# board.net
KiCad netlist of a schematic drawn in EAGLE
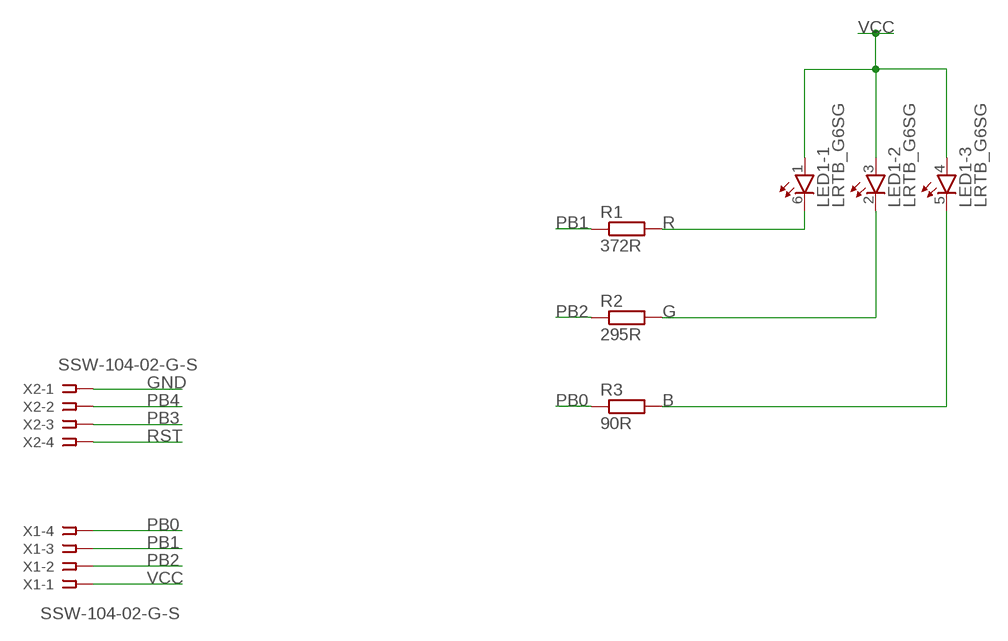
[diagram p0: schematic, sheet 1]

(export (version "E")
  (design (tool "Eeschema 10.0.6"))
  (components
    (comp (ref "LED1")
      (value "LRTB_G6SG")
      (footprint "eagle-import:LRTB_G6SG")
      (libsource (lib "eagle-import") (part "LRTB_G6SG"))
    )
    (comp (ref "R1")
      (value "372R")
      (footprint "eagle-import:R1206")
      (libsource (lib "eagle-import") (part "R-EU_R1206"))
    )
    (comp (ref "R2")
      (value "295R")
      (footprint "eagle-import:R1206")
      (libsource (lib "eagle-import") (part "R-EU_R1206"))
    )
    (comp (ref "R3")
      (value "90R")
      (footprint "eagle-import:R1206")
      (libsource (lib "eagle-import") (part "R-EU_R1206"))
    )
    (comp (ref "X1")
      (value "SSW-104-02-G-S")
      (footprint "eagle-import:SSW-104-02-G-S")
      (fields (field (name "MF") "Samtec Inc."))
      (libsource (lib "eagle-import") (part "SSW-104-02-G-S"))
    )
    (comp (ref "X2")
      (value "SSW-104-02-G-S")
      (footprint "eagle-import:SSW-104-02-G-S")
      (fields (field (name "MF") "Samtec Inc."))
      (libsource (lib "eagle-import") (part "SSW-104-02-G-S"))
    )
  )
  (nets
    (net (code "1") (name "/B") (class "Default")
      (node (ref "LED1") (pin "5") (pinfunction "C_5") (pintype "passive"))
      (node (ref "R3") (pin "2") (pinfunction "2_2") (pintype "passive"))
    )
    (net (code "2") (name "/G") (class "Default")
      (node (ref "LED1") (pin "2") (pinfunction "C_2") (pintype "passive"))
      (node (ref "R2") (pin "2") (pinfunction "2_2") (pintype "passive"))
    )
    (net (code "3") (name "/GND") (class "Default")
      (node (ref "X2") (pin "1") (pinfunction "1_1") (pintype "passive"))
    )
    (net (code "4") (name "/PB0") (class "Default")
      (node (ref "R3") (pin "1") (pinfunction "1_1") (pintype "passive"))
      (node (ref "X1") (pin "4") (pinfunction "1_4") (pintype "passive"))
    )
    (net (code "5") (name "/PB1") (class "Default")
      (node (ref "R1") (pin "1") (pinfunction "1_1") (pintype "passive"))
      (node (ref "X1") (pin "3") (pinfunction "1_3") (pintype "passive"))
    )
    (net (code "6") (name "/PB2") (class "Default")
      (node (ref "R2") (pin "1") (pinfunction "1_1") (pintype "passive"))
      (node (ref "X1") (pin "2") (pinfunction "1_2") (pintype "passive"))
    )
    (net (code "7") (name "/PB3") (class "Default")
      (node (ref "X2") (pin "3") (pinfunction "1_3") (pintype "passive"))
    )
    (net (code "8") (name "/PB4") (class "Default")
      (node (ref "X2") (pin "2") (pinfunction "1_2") (pintype "passive"))
    )
    (net (code "9") (name "/R") (class "Default")
      (node (ref "LED1") (pin "6") (pinfunction "C_6") (pintype "passive"))
      (node (ref "R1") (pin "2") (pinfunction "2_2") (pintype "passive"))
    )
    (net (code "10") (name "/RST") (class "Default")
      (node (ref "X2") (pin "4") (pinfunction "1_4") (pintype "passive"))
    )
    (net (code "11") (name "/VCC") (class "Default")
      (node (ref "LED1") (pin "1") (pinfunction "A_1") (pintype "passive"))
      (node (ref "LED1") (pin "3") (pinfunction "A_3") (pintype "passive"))
      (node (ref "LED1") (pin "4") (pinfunction "A_4") (pintype "passive"))
      (node (ref "X1") (pin "1") (pinfunction "1_1") (pintype "passive"))
    )
  )
)
